# Microcontroller.net
KiCad netlist of a schematic drawn in EAGLE
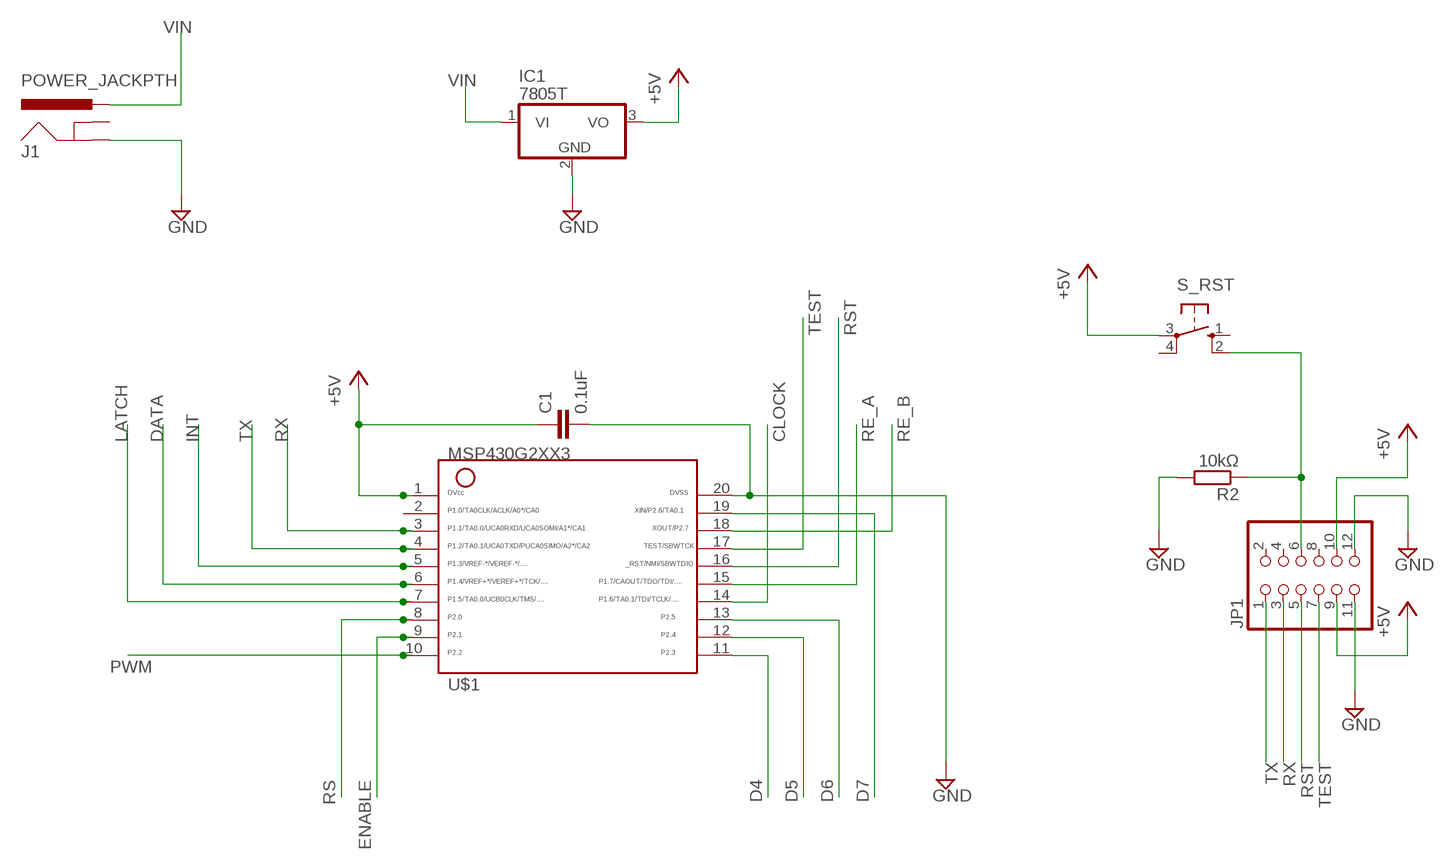
[diagram p0: schematic, sheet 1]

(export (version "E")
  (design (tool "Eeschema 10.0.6"))
  (components
    (comp (ref "C1")
      (value "0.1uF")
      (footprint "eagle-import:C025-025X050")
      (libsource (lib "eagle-import") (part "C-EU025-025X050"))
    )
    (comp (ref "IC1")
      (value "7805T")
      (footprint "eagle-import:TO220H")
      (libsource (lib "eagle-import") (part "78T05"))
    )
    (comp (ref "J1")
      (value "POWER_JACKPTH")
      (footprint "eagle-import:POWER_JACK_PTH")
      (libsource (lib "eagle-import") (part "POWER_JACKPTH"))
    )
    (comp (ref "JP1")
      (value "PINHD-2X6")
      (footprint "eagle-import:2X06")
      (libsource (lib "eagle-import") (part "PINHD-2X6"))
    )
    (comp (ref "R2")
      (value "10kΩ")
      (footprint "eagle-import:0207_10")
      (libsource (lib "eagle-import") (part "R-EU_0207/10"))
    )
    (comp (ref "S_RST")
      (value "10-XX")
      (footprint "eagle-import:B3F-10XX")
      (fields (field (name "MPN") "B3F-1000"))
      (libsource (lib "eagle-import") (part "10-XX"))
    )
    (comp (ref "U$1")
      (value "G2XX3---N20")
      (footprint "eagle-import:N20")
      (libsource (lib "eagle-import") (part "G2XX3---N20"))
    )
  )
  (nets
    (net (code "1") (name "+5V") (class "Default")
      (node (ref "C1") (pin "1") (pinfunction "1_1") (pintype "passive"))
      (node (ref "IC1") (pin "3") (pinfunction "VO_3") (pintype "passive"))
      (node (ref "JP1") (pin "10") (pinfunction "10_10") (pintype "passive"))
      (node (ref "JP1") (pin "9") (pinfunction "9_9") (pintype "passive"))
      (node (ref "S_RST") (pin "3") (pinfunction "P_3") (pintype "passive"))
      (node (ref "U$1") (pin "1") (pinfunction "1_1") (pintype "bidirectional"))
    )
    (net (code "2") (name "/CLOCK") (class "Default")
      (node (ref "U$1") (pin "14") (pinfunction "14_14") (pintype "bidirectional"))
    )
    (net (code "3") (name "/D4") (class "Default")
      (node (ref "U$1") (pin "11") (pinfunction "11_11") (pintype "bidirectional"))
    )
    (net (code "4") (name "/D5") (class "Default")
      (node (ref "U$1") (pin "12") (pinfunction "12_12") (pintype "bidirectional"))
    )
    (net (code "5") (name "/D6") (class "Default")
      (node (ref "U$1") (pin "13") (pinfunction "13_13") (pintype "bidirectional"))
    )
    (net (code "6") (name "/D7") (class "Default")
      (node (ref "U$1") (pin "19") (pinfunction "19_19") (pintype "bidirectional"))
    )
    (net (code "7") (name "/DATA") (class "Default")
      (node (ref "U$1") (pin "6") (pinfunction "6_6") (pintype "bidirectional"))
    )
    (net (code "8") (name "/ENABLE") (class "Default")
      (node (ref "U$1") (pin "9") (pinfunction "9_9") (pintype "bidirectional"))
    )
    (net (code "9") (name "/INT") (class "Default")
      (node (ref "U$1") (pin "5") (pinfunction "5_5") (pintype "bidirectional"))
    )
    (net (code "10") (name "/LATCH") (class "Default")
      (node (ref "U$1") (pin "7") (pinfunction "7_7") (pintype "bidirectional"))
    )
    (net (code "11") (name "/PWM") (class "Default")
      (node (ref "U$1") (pin "10") (pinfunction "10_10") (pintype "bidirectional"))
    )
    (net (code "12") (name "/RE_A") (class "Default")
      (node (ref "U$1") (pin "15") (pinfunction "15_15") (pintype "bidirectional"))
    )
    (net (code "13") (name "/RE_B") (class "Default")
      (node (ref "U$1") (pin "18") (pinfunction "18_18") (pintype "bidirectional"))
    )
    (net (code "14") (name "/RS") (class "Default")
      (node (ref "U$1") (pin "8") (pinfunction "8_8") (pintype "bidirectional"))
    )
    (net (code "15") (name "/RST") (class "Default")
      (node (ref "JP1") (pin "5") (pinfunction "5_5") (pintype "passive"))
      (node (ref "U$1") (pin "16") (pinfunction "16_16") (pintype "bidirectional"))
    )
    (net (code "16") (name "/RX") (class "Default")
      (node (ref "JP1") (pin "3") (pinfunction "3_3") (pintype "passive"))
      (node (ref "U$1") (pin "3") (pinfunction "3_3") (pintype "bidirectional"))
    )
    (net (code "17") (name "/TEST") (class "Default")
      (node (ref "JP1") (pin "7") (pinfunction "7_7") (pintype "passive"))
      (node (ref "U$1") (pin "17") (pinfunction "17_17") (pintype "bidirectional"))
    )
    (net (code "18") (name "/TX") (class "Default")
      (node (ref "JP1") (pin "1") (pinfunction "1_1") (pintype "passive"))
      (node (ref "U$1") (pin "4") (pinfunction "4_4") (pintype "bidirectional"))
    )
    (net (code "19") (name "/VIN") (class "Default")
      (node (ref "IC1") (pin "1") (pinfunction "VI_1") (pintype "input"))
      (node (ref "J1") (pin "PWR") (pinfunction "PWR_PWR") (pintype "bidirectional"))
    )
    (net (code "20") (name "GND") (class "Default")
      (node (ref "C1") (pin "2") (pinfunction "2_2") (pintype "passive"))
      (node (ref "IC1") (pin "2") (pinfunction "GND_2") (pintype "passive"))
      (node (ref "J1") (pin "GND") (pinfunction "GND_GND") (pintype "bidirectional"))
      (node (ref "JP1") (pin "11") (pinfunction "11_11") (pintype "passive"))
      (node (ref "JP1") (pin "12") (pinfunction "12_12") (pintype "passive"))
      (node (ref "R2") (pin "2") (pinfunction "2_2") (pintype "passive"))
      (node (ref "U$1") (pin "20") (pinfunction "20_20") (pintype "bidirectional"))
    )
    (net (code "21") (name "Net-(S_RST-S1)") (class "Default")
      (node (ref "JP1") (pin "6") (pinfunction "6_6") (pintype "passive"))
      (node (ref "R2") (pin "1") (pinfunction "1_1") (pintype "passive"))
      (node (ref "S_RST") (pin "2") (pinfunction "S1_2") (pintype "passive"))
    )
    (net (code "22") (name "unconnected-(J1-PadGNDBREAK)") (class "Default")
      (node (ref "J1") (pin "GNDBREAK") (pinfunction "GNDBREAK_GNDBREAK") (pintype "bidirectional"))
    )
    (net (code "23") (name "unconnected-(JP1-Pad2)") (class "Default")
      (node (ref "JP1") (pin "2") (pinfunction "2_2") (pintype "passive"))
    )
    (net (code "24") (name "unconnected-(JP1-Pad4)") (class "Default")
      (node (ref "JP1") (pin "4") (pinfunction "4_4") (pintype "passive"))
    )
    (net (code "25") (name "unconnected-(JP1-Pad8)") (class "Default")
      (node (ref "JP1") (pin "8") (pinfunction "8_8") (pintype "passive"))
    )
    (net (code "26") (name "unconnected-(S_RST-P1-Pad4)") (class "Default")
      (node (ref "S_RST") (pin "4") (pinfunction "P1_4") (pintype "passive"))
    )
    (net (code "27") (name "unconnected-(S_RST-S-Pad1)") (class "Default")
      (node (ref "S_RST") (pin "1") (pinfunction "S_1") (pintype "passive"))
    )
    (net (code "28") (name "unconnected-(U$1-Pad2)") (class "Default")
      (node (ref "U$1") (pin "2") (pinfunction "2_2") (pintype "bidirectional"))
    )
  )
)
